# SCH_EBike-Controller_2024-08-19.net
KiCad netlist of a schematic drawn in EasyEDA
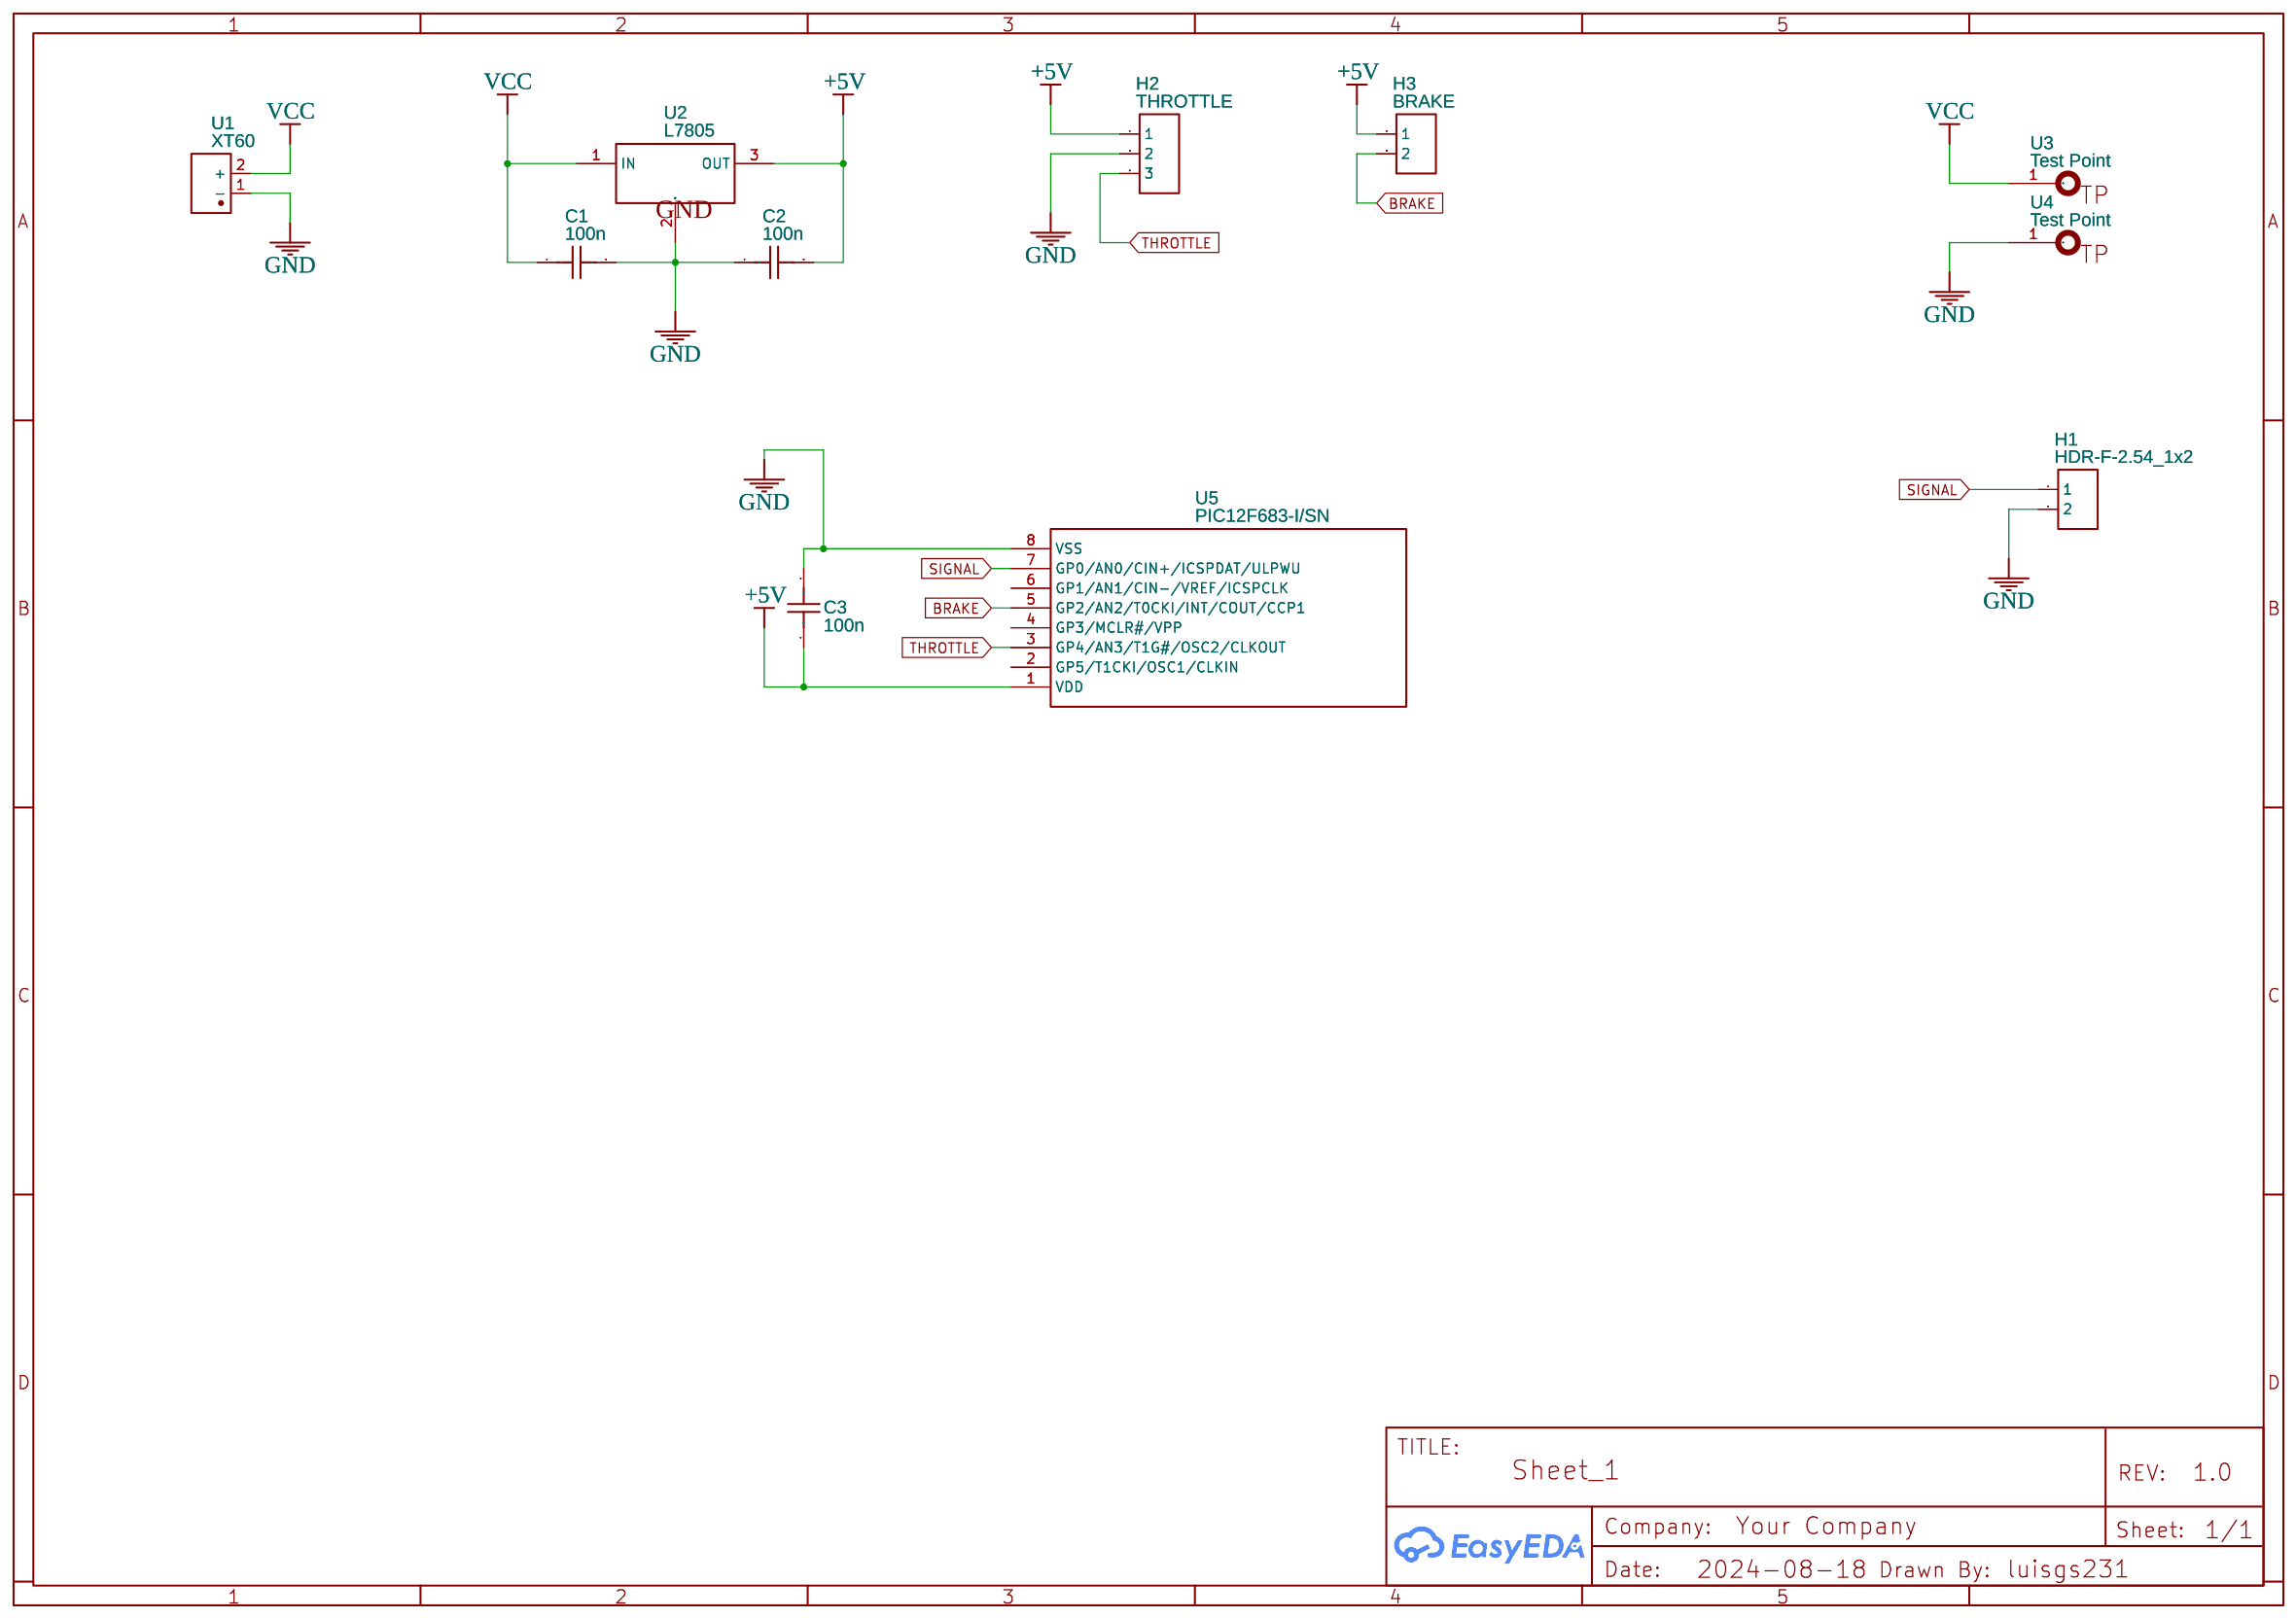
[diagram p0: schematic sheet]

(export (version "E")
  (design (tool "Eeschema 10.0.6"))
  (components
    (comp (ref "C1") (value "100n") (libsource (lib "") (part "C_1206_US_1")))
    (comp (ref "C2") (value "100n") (libsource (lib "") (part "C_1206_US_1")))
    (comp (ref "C3") (value "100n") (libsource (lib "") (part "C_1206_US")))
    (comp (ref "H1") (value "HDR-F-2.54_1x2") (libsource (lib "") (part "HDR-F-2.54_1x2")))
    (comp (ref "H2") (value "THROTTLE") (libsource (lib "") (part "HDR-F-2.54_1x3")))
    (comp (ref "H3") (value "BRAKE") (libsource (lib "") (part "HDR-F-2.54_1x2")))
    (comp (ref "U1")
      (value "XT60")
      (fields (field (name "Manufacturer") "AMASS(艾迈斯)"))
      (libsource (lib "") (part "XT60"))
    )
    (comp (ref "U2")
      (value "L7805")
      (fields (field (name "Manufacturer") "SY(顺烨）"))
      (libsource (lib "") (part "L7805"))
    )
    (comp (ref "U3") (value "Test Point") (libsource (lib "") (part "Test Point")))
    (comp (ref "U4") (value "Test Point") (libsource (lib "") (part "Test Point")))
    (comp (ref "U5")
      (value "PIC12F683-I/SN")
      (fields (field (name "Manufacturer") "MICROCHIP"))
      (libsource (lib "") (part "PIC12F683-I/SN"))
    )
  )
  (nets
    (net (code "1") (name "+5V") (class "Default")
      (node (ref "C2") (pin "2") (pinfunction "2_2") (pintype "unspecified"))
      (node (ref "C3") (pin "2") (pinfunction "2_2") (pintype "unspecified"))
      (node (ref "H2") (pin "1") (pinfunction "1_1") (pintype "input"))
      (node (ref "H3") (pin "1") (pinfunction "1_1") (pintype "input"))
      (node (ref "U2") (pin "3") (pinfunction "OUT_3") (pintype "passive"))
      (node (ref "U5") (pin "1") (pinfunction "VDD_1") (pintype "unspecified"))
    )
    (net (code "2") (name "BRAKE") (class "Default")
      (node (ref "H3") (pin "2") (pinfunction "2_2") (pintype "input"))
      (node (ref "U5") (pin "5") (pinfunction "GP2/AN2/T0CKI/INT/COUT/CCP1_5") (pintype "unspecified"))
    )
    (net (code "3") (name "GND") (class "Default")
      (node (ref "C1") (pin "2") (pinfunction "2_2") (pintype "unspecified"))
      (node (ref "C2") (pin "1") (pinfunction "1_1") (pintype "unspecified"))
      (node (ref "C3") (pin "1") (pinfunction "1_1") (pintype "unspecified"))
      (node (ref "H1") (pin "2") (pinfunction "2_2") (pintype "input"))
      (node (ref "H2") (pin "2") (pinfunction "2_2") (pintype "input"))
      (node (ref "U1") (pin "1") (pinfunction "-_1") (pintype "unspecified"))
      (node (ref "U2") (pin "2") (pinfunction "GND_2") (pintype "passive"))
      (node (ref "U4") (pin "1") (pinfunction "TP_1") (pintype "unspecified"))
      (node (ref "U5") (pin "8") (pinfunction "VSS_8") (pintype "unspecified"))
    )
    (net (code "4") (name "SIGNAL") (class "Default")
      (node (ref "H1") (pin "1") (pinfunction "1_1") (pintype "input"))
      (node (ref "U5") (pin "7") (pinfunction "GP0/AN0/CIN+/ICSPDAT/ULPWU_7") (pintype "unspecified"))
    )
    (net (code "5") (name "THROTTLE") (class "Default")
      (node (ref "H2") (pin "3") (pinfunction "3_3") (pintype "input"))
      (node (ref "U5") (pin "3") (pinfunction "GP4/AN3/T1G#/OSC2/CLKOUT_3") (pintype "unspecified"))
    )
    (net (code "6") (name "VCC") (class "Default")
      (node (ref "C1") (pin "1") (pinfunction "1_1") (pintype "unspecified"))
      (node (ref "U1") (pin "2") (pinfunction "+_2") (pintype "unspecified"))
      (node (ref "U2") (pin "1") (pinfunction "IN_1") (pintype "passive"))
      (node (ref "U3") (pin "1") (pinfunction "TP_1") (pintype "unspecified"))
    )
    (net (code "7") (name "unconnected-(U5-GP1{slash}AN1{slash}CIN-{slash}VREF{slash}ICSPCLK-Pad6)") (class "Default")
      (node (ref "U5") (pin "6") (pinfunction "GP1/AN1/CIN-/VREF/ICSPCLK_6") (pintype "unspecified"))
    )
    (net (code "8") (name "unconnected-(U5-GP3{slash}MCLR#{slash}VPP-Pad4)") (class "Default")
      (node (ref "U5") (pin "4") (pinfunction "GP3/MCLR#/VPP_4") (pintype "unspecified"))
    )
    (net (code "9") (name "unconnected-(U5-GP5{slash}T1CKI{slash}OSC1{slash}CLKIN-Pad2)") (class "Default")
      (node (ref "U5") (pin "2") (pinfunction "GP5/T1CKI/OSC1/CLKIN_2") (pintype "unspecified"))
    )
  )
)
